# led.net
KiCad netlist of a schematic drawn in EAGLE
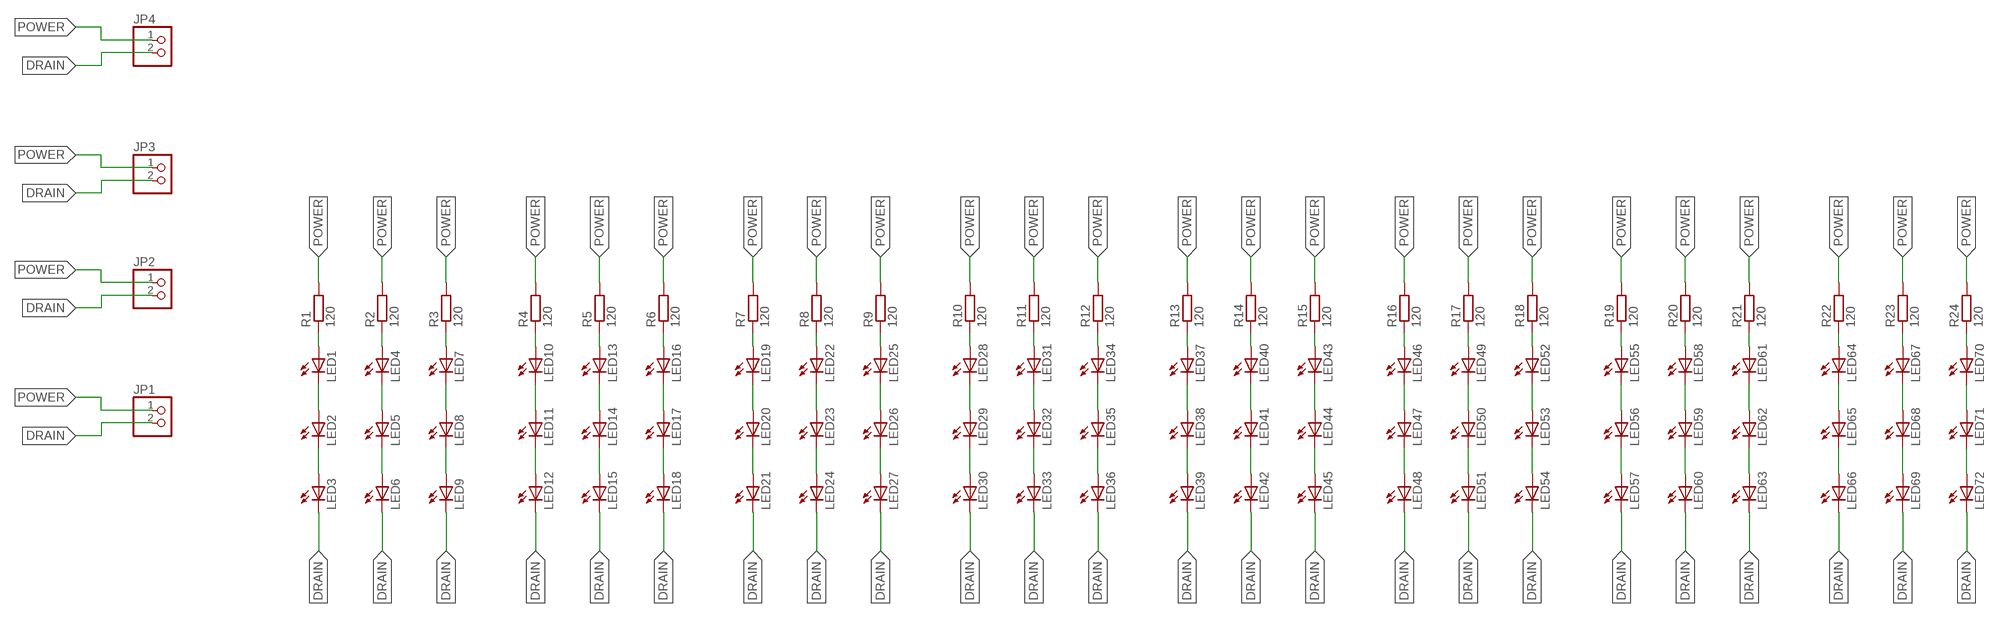
[diagram p0: schematic, sheet 1]

(export (version "E")
  (design (tool "Eeschema 10.0.6"))
  (components
    (comp (ref "JP1")
      (value "PINHD-1X2")
      (footprint "eagle-import:1X02")
      (libsource (lib "eagle-import") (part "PINHD-1X2"))
    )
    (comp (ref "JP2")
      (value "PINHD-1X2")
      (footprint "eagle-import:1X02")
      (libsource (lib "eagle-import") (part "PINHD-1X2"))
    )
    (comp (ref "JP3")
      (value "PINHD-1X2")
      (footprint "eagle-import:1X02")
      (libsource (lib "eagle-import") (part "PINHD-1X2"))
    )
    (comp (ref "JP4")
      (value "PINHD-1X2")
      (footprint "eagle-import:1X02")
      (libsource (lib "eagle-import") (part "PINHD-1X2"))
    )
    (comp (ref "LED1")
      (value "LED5MM")
      (footprint "eagle-import:LED5MM")
      (libsource (lib "eagle-import") (part "LED5MM"))
    )
    (comp (ref "LED2")
      (value "LED5MM")
      (footprint "eagle-import:LED5MM")
      (libsource (lib "eagle-import") (part "LED5MM"))
    )
    (comp (ref "LED3")
      (value "LED5MM")
      (footprint "eagle-import:LED5MM")
      (libsource (lib "eagle-import") (part "LED5MM"))
    )
    (comp (ref "LED4")
      (value "LED5MM")
      (footprint "eagle-import:LED5MM")
      (libsource (lib "eagle-import") (part "LED5MM"))
    )
    (comp (ref "LED5")
      (value "LED5MM")
      (footprint "eagle-import:LED5MM")
      (libsource (lib "eagle-import") (part "LED5MM"))
    )
    (comp (ref "LED6")
      (value "LED5MM")
      (footprint "eagle-import:LED5MM")
      (libsource (lib "eagle-import") (part "LED5MM"))
    )
    (comp (ref "LED7")
      (value "LED5MM")
      (footprint "eagle-import:LED5MM")
      (libsource (lib "eagle-import") (part "LED5MM"))
    )
    (comp (ref "LED8")
      (value "LED5MM")
      (footprint "eagle-import:LED5MM")
      (libsource (lib "eagle-import") (part "LED5MM"))
    )
    (comp (ref "LED9")
      (value "LED5MM")
      (footprint "eagle-import:LED5MM")
      (libsource (lib "eagle-import") (part "LED5MM"))
    )
    (comp (ref "LED10")
      (value "LED5MM")
      (footprint "eagle-import:LED5MM")
      (libsource (lib "eagle-import") (part "LED5MM"))
    )
    (comp (ref "LED11")
      (value "LED5MM")
      (footprint "eagle-import:LED5MM")
      (libsource (lib "eagle-import") (part "LED5MM"))
    )
    (comp (ref "LED12")
      (value "LED5MM")
      (footprint "eagle-import:LED5MM")
      (libsource (lib "eagle-import") (part "LED5MM"))
    )
    (comp (ref "LED13")
      (value "LED5MM")
      (footprint "eagle-import:LED5MM")
      (libsource (lib "eagle-import") (part "LED5MM"))
    )
    (comp (ref "LED14")
      (value "LED5MM")
      (footprint "eagle-import:LED5MM")
      (libsource (lib "eagle-import") (part "LED5MM"))
    )
    (comp (ref "LED15")
      (value "LED5MM")
      (footprint "eagle-import:LED5MM")
      (libsource (lib "eagle-import") (part "LED5MM"))
    )
    (comp (ref "LED16")
      (value "LED5MM")
      (footprint "eagle-import:LED5MM")
      (libsource (lib "eagle-import") (part "LED5MM"))
    )
    (comp (ref "LED17")
      (value "LED5MM")
      (footprint "eagle-import:LED5MM")
      (libsource (lib "eagle-import") (part "LED5MM"))
    )
    (comp (ref "LED18")
      (value "LED5MM")
      (footprint "eagle-import:LED5MM")
      (libsource (lib "eagle-import") (part "LED5MM"))
    )
    (comp (ref "LED19")
      (value "LED5MM")
      (footprint "eagle-import:LED5MM")
      (libsource (lib "eagle-import") (part "LED5MM"))
    )
    (comp (ref "LED20")
      (value "LED5MM")
      (footprint "eagle-import:LED5MM")
      (libsource (lib "eagle-import") (part "LED5MM"))
    )
    (comp (ref "LED21")
      (value "LED5MM")
      (footprint "eagle-import:LED5MM")
      (libsource (lib "eagle-import") (part "LED5MM"))
    )
    (comp (ref "LED22")
      (value "LED5MM")
      (footprint "eagle-import:LED5MM")
      (libsource (lib "eagle-import") (part "LED5MM"))
    )
    (comp (ref "LED23")
      (value "LED5MM")
      (footprint "eagle-import:LED5MM")
      (libsource (lib "eagle-import") (part "LED5MM"))
    )
    (comp (ref "LED24")
      (value "LED5MM")
      (footprint "eagle-import:LED5MM")
      (libsource (lib "eagle-import") (part "LED5MM"))
    )
    (comp (ref "LED25")
      (value "LED5MM")
      (footprint "eagle-import:LED5MM")
      (libsource (lib "eagle-import") (part "LED5MM"))
    )
    (comp (ref "LED26")
      (value "LED5MM")
      (footprint "eagle-import:LED5MM")
      (libsource (lib "eagle-import") (part "LED5MM"))
    )
    (comp (ref "LED27")
      (value "LED5MM")
      (footprint "eagle-import:LED5MM")
      (libsource (lib "eagle-import") (part "LED5MM"))
    )
    (comp (ref "LED28")
      (value "LED5MM")
      (footprint "eagle-import:LED5MM")
      (libsource (lib "eagle-import") (part "LED5MM"))
    )
    (comp (ref "LED29")
      (value "LED5MM")
      (footprint "eagle-import:LED5MM")
      (libsource (lib "eagle-import") (part "LED5MM"))
    )
    (comp (ref "LED30")
      (value "LED5MM")
      (footprint "eagle-import:LED5MM")
      (libsource (lib "eagle-import") (part "LED5MM"))
    )
    (comp (ref "LED31")
      (value "LED5MM")
      (footprint "eagle-import:LED5MM")
      (libsource (lib "eagle-import") (part "LED5MM"))
    )
    (comp (ref "LED32")
      (value "LED5MM")
      (footprint "eagle-import:LED5MM")
      (libsource (lib "eagle-import") (part "LED5MM"))
    )
    (comp (ref "LED33")
      (value "LED5MM")
      (footprint "eagle-import:LED5MM")
      (libsource (lib "eagle-import") (part "LED5MM"))
    )
    (comp (ref "LED34")
      (value "LED5MM")
      (footprint "eagle-import:LED5MM")
      (libsource (lib "eagle-import") (part "LED5MM"))
    )
    (comp (ref "LED35")
      (value "LED5MM")
      (footprint "eagle-import:LED5MM")
      (libsource (lib "eagle-import") (part "LED5MM"))
    )
    (comp (ref "LED36")
      (value "LED5MM")
      (footprint "eagle-import:LED5MM")
      (libsource (lib "eagle-import") (part "LED5MM"))
    )
    (comp (ref "LED37")
      (value "LED5MM")
      (footprint "eagle-import:LED5MM")
      (libsource (lib "eagle-import") (part "LED5MM"))
    )
    (comp (ref "LED38")
      (value "LED5MM")
      (footprint "eagle-import:LED5MM")
      (libsource (lib "eagle-import") (part "LED5MM"))
    )
    (comp (ref "LED39")
      (value "LED5MM")
      (footprint "eagle-import:LED5MM")
      (libsource (lib "eagle-import") (part "LED5MM"))
    )
    (comp (ref "LED40")
      (value "LED5MM")
      (footprint "eagle-import:LED5MM")
      (libsource (lib "eagle-import") (part "LED5MM"))
    )
    (comp (ref "LED41")
      (value "LED5MM")
      (footprint "eagle-import:LED5MM")
      (libsource (lib "eagle-import") (part "LED5MM"))
    )
    (comp (ref "LED42")
      (value "LED5MM")
      (footprint "eagle-import:LED5MM")
      (libsource (lib "eagle-import") (part "LED5MM"))
    )
    (comp (ref "LED43")
      (value "LED5MM")
      (footprint "eagle-import:LED5MM")
      (libsource (lib "eagle-import") (part "LED5MM"))
    )
    (comp (ref "LED44")
      (value "LED5MM")
      (footprint "eagle-import:LED5MM")
      (libsource (lib "eagle-import") (part "LED5MM"))
    )
    (comp (ref "LED45")
      (value "LED5MM")
      (footprint "eagle-import:LED5MM")
      (libsource (lib "eagle-import") (part "LED5MM"))
    )
    (comp (ref "LED46")
      (value "LED5MM")
      (footprint "eagle-import:LED5MM")
      (libsource (lib "eagle-import") (part "LED5MM"))
    )
    (comp (ref "LED47")
      (value "LED5MM")
      (footprint "eagle-import:LED5MM")
      (libsource (lib "eagle-import") (part "LED5MM"))
    )
    (comp (ref "LED48")
      (value "LED5MM")
      (footprint "eagle-import:LED5MM")
      (libsource (lib "eagle-import") (part "LED5MM"))
    )
    (comp (ref "LED49")
      (value "LED5MM")
      (footprint "eagle-import:LED5MM")
      (libsource (lib "eagle-import") (part "LED5MM"))
    )
    (comp (ref "LED50")
      (value "LED5MM")
      (footprint "eagle-import:LED5MM")
      (libsource (lib "eagle-import") (part "LED5MM"))
    )
    (comp (ref "LED51")
      (value "LED5MM")
      (footprint "eagle-import:LED5MM")
      (libsource (lib "eagle-import") (part "LED5MM"))
    )
    (comp (ref "LED52")
      (value "LED5MM")
      (footprint "eagle-import:LED5MM")
      (libsource (lib "eagle-import") (part "LED5MM"))
    )
    (comp (ref "LED53")
      (value "LED5MM")
      (footprint "eagle-import:LED5MM")
      (libsource (lib "eagle-import") (part "LED5MM"))
    )
    (comp (ref "LED54")
      (value "LED5MM")
      (footprint "eagle-import:LED5MM")
      (libsource (lib "eagle-import") (part "LED5MM"))
    )
    (comp (ref "LED55")
      (value "LED5MM")
      (footprint "eagle-import:LED5MM")
      (libsource (lib "eagle-import") (part "LED5MM"))
    )
    (comp (ref "LED56")
      (value "LED5MM")
      (footprint "eagle-import:LED5MM")
      (libsource (lib "eagle-import") (part "LED5MM"))
    )
    (comp (ref "LED57")
      (value "LED5MM")
      (footprint "eagle-import:LED5MM")
      (libsource (lib "eagle-import") (part "LED5MM"))
    )
    (comp (ref "LED58")
      (value "LED5MM")
      (footprint "eagle-import:LED5MM")
      (libsource (lib "eagle-import") (part "LED5MM"))
    )
    (comp (ref "LED59")
      (value "LED5MM")
      (footprint "eagle-import:LED5MM")
      (libsource (lib "eagle-import") (part "LED5MM"))
    )
    (comp (ref "LED60")
      (value "LED5MM")
      (footprint "eagle-import:LED5MM")
      (libsource (lib "eagle-import") (part "LED5MM"))
    )
    (comp (ref "LED61")
      (value "LED5MM")
      (footprint "eagle-import:LED5MM")
      (libsource (lib "eagle-import") (part "LED5MM"))
    )
    (comp (ref "LED62")
      (value "LED5MM")
      (footprint "eagle-import:LED5MM")
      (libsource (lib "eagle-import") (part "LED5MM"))
    )
    (comp (ref "LED63")
      (value "LED5MM")
      (footprint "eagle-import:LED5MM")
      (libsource (lib "eagle-import") (part "LED5MM"))
    )
    (comp (ref "LED64")
      (value "LED5MM")
      (footprint "eagle-import:LED5MM")
      (libsource (lib "eagle-import") (part "LED5MM"))
    )
    (comp (ref "LED65")
      (value "LED5MM")
      (footprint "eagle-import:LED5MM")
      (libsource (lib "eagle-import") (part "LED5MM"))
    )
    (comp (ref "LED66")
      (value "LED5MM")
      (footprint "eagle-import:LED5MM")
      (libsource (lib "eagle-import") (part "LED5MM"))
    )
    (comp (ref "LED67")
      (value "LED5MM")
      (footprint "eagle-import:LED5MM")
      (libsource (lib "eagle-import") (part "LED5MM"))
    )
    (comp (ref "LED68")
      (value "LED5MM")
      (footprint "eagle-import:LED5MM")
      (libsource (lib "eagle-import") (part "LED5MM"))
    )
    (comp (ref "LED69")
      (value "LED5MM")
      (footprint "eagle-import:LED5MM")
      (libsource (lib "eagle-import") (part "LED5MM"))
    )
    (comp (ref "LED70")
      (value "LED5MM")
      (footprint "eagle-import:LED5MM")
      (libsource (lib "eagle-import") (part "LED5MM"))
    )
    (comp (ref "LED71")
      (value "LED5MM")
      (footprint "eagle-import:LED5MM")
      (libsource (lib "eagle-import") (part "LED5MM"))
    )
    (comp (ref "LED72")
      (value "LED5MM")
      (footprint "eagle-import:LED5MM")
      (libsource (lib "eagle-import") (part "LED5MM"))
    )
    (comp (ref "R1")
      (value "120")
      (footprint "eagle-import:R0805")
      (libsource (lib "eagle-import") (part "R-EU_R0805"))
    )
    (comp (ref "R2")
      (value "120")
      (footprint "eagle-import:R0805")
      (libsource (lib "eagle-import") (part "R-EU_R0805"))
    )
    (comp (ref "R3")
      (value "120")
      (footprint "eagle-import:R0805")
      (libsource (lib "eagle-import") (part "R-EU_R0805"))
    )
    (comp (ref "R4")
      (value "120")
      (footprint "eagle-import:R0805")
      (libsource (lib "eagle-import") (part "R-EU_R0805"))
    )
    (comp (ref "R5")
      (value "120")
      (footprint "eagle-import:R0805")
      (libsource (lib "eagle-import") (part "R-EU_R0805"))
    )
    (comp (ref "R6")
      (value "120")
      (footprint "eagle-import:R0805")
      (libsource (lib "eagle-import") (part "R-EU_R0805"))
    )
    (comp (ref "R7")
      (value "120")
      (footprint "eagle-import:R0805")
      (libsource (lib "eagle-import") (part "R-EU_R0805"))
    )
    (comp (ref "R8")
      (value "120")
      (footprint "eagle-import:R0805")
      (libsource (lib "eagle-import") (part "R-EU_R0805"))
    )
    (comp (ref "R9")
      (value "120")
      (footprint "eagle-import:R0805")
      (libsource (lib "eagle-import") (part "R-EU_R0805"))
    )
    (comp (ref "R10")
      (value "120")
      (footprint "eagle-import:R0805")
      (libsource (lib "eagle-import") (part "R-EU_R0805"))
    )
    (comp (ref "R11")
      (value "120")
      (footprint "eagle-import:R0805")
      (libsource (lib "eagle-import") (part "R-EU_R0805"))
    )
    (comp (ref "R12")
      (value "120")
      (footprint "eagle-import:R0805")
      (libsource (lib "eagle-import") (part "R-EU_R0805"))
    )
    (comp (ref "R13")
      (value "120")
      (footprint "eagle-import:R0805")
      (libsource (lib "eagle-import") (part "R-EU_R0805"))
    )
    (comp (ref "R14")
      (value "120")
      (footprint "eagle-import:R0805")
      (libsource (lib "eagle-import") (part "R-EU_R0805"))
    )
    (comp (ref "R15")
      (value "120")
      (footprint "eagle-import:R0805")
      (libsource (lib "eagle-import") (part "R-EU_R0805"))
    )
    (comp (ref "R16")
      (value "120")
      (footprint "eagle-import:R0805")
      (libsource (lib "eagle-import") (part "R-EU_R0805"))
    )
    (comp (ref "R17")
      (value "120")
      (footprint "eagle-import:R0805")
      (libsource (lib "eagle-import") (part "R-EU_R0805"))
    )
    (comp (ref "R18")
      (value "120")
      (footprint "eagle-import:R0805")
      (libsource (lib "eagle-import") (part "R-EU_R0805"))
    )
    (comp (ref "R19")
      (value "120")
      (footprint "eagle-import:R0805")
      (libsource (lib "eagle-import") (part "R-EU_R0805"))
    )
    (comp (ref "R20")
      (value "120")
      (footprint "eagle-import:R0805")
      (libsource (lib "eagle-import") (part "R-EU_R0805"))
    )
    (comp (ref "R21")
      (value "120")
      (footprint "eagle-import:R0805")
      (libsource (lib "eagle-import") (part "R-EU_R0805"))
    )
    (comp (ref "R22")
      (value "120")
      (footprint "eagle-import:R0805")
      (libsource (lib "eagle-import") (part "R-EU_R0805"))
    )
    (comp (ref "R23")
      (value "120")
      (footprint "eagle-import:R0805")
      (libsource (lib "eagle-import") (part "R-EU_R0805"))
    )
    (comp (ref "R24")
      (value "120")
      (footprint "eagle-import:R0805")
      (libsource (lib "eagle-import") (part "R-EU_R0805"))
    )
  )
  (nets
    (net (code "1") (name "DRAIN") (class "Default")
      (node (ref "JP1") (pin "2") (pinfunction "2_2") (pintype "passive"))
      (node (ref "JP2") (pin "2") (pinfunction "2_2") (pintype "passive"))
      (node (ref "JP3") (pin "2") (pinfunction "2_2") (pintype "passive"))
      (node (ref "JP4") (pin "2") (pinfunction "2_2") (pintype "passive"))
      (node (ref "LED12") (pin "K") (pinfunction "C_K") (pintype "passive"))
      (node (ref "LED15") (pin "K") (pinfunction "C_K") (pintype "passive"))
      (node (ref "LED18") (pin "K") (pinfunction "C_K") (pintype "passive"))
      (node (ref "LED21") (pin "K") (pinfunction "C_K") (pintype "passive"))
      (node (ref "LED24") (pin "K") (pinfunction "C_K") (pintype "passive"))
      (node (ref "LED27") (pin "K") (pinfunction "C_K") (pintype "passive"))
      (node (ref "LED3") (pin "K") (pinfunction "C_K") (pintype "passive"))
      (node (ref "LED30") (pin "K") (pinfunction "C_K") (pintype "passive"))
      (node (ref "LED33") (pin "K") (pinfunction "C_K") (pintype "passive"))
      (node (ref "LED36") (pin "K") (pinfunction "C_K") (pintype "passive"))
      (node (ref "LED39") (pin "K") (pinfunction "C_K") (pintype "passive"))
      (node (ref "LED42") (pin "K") (pinfunction "C_K") (pintype "passive"))
      (node (ref "LED45") (pin "K") (pinfunction "C_K") (pintype "passive"))
      (node (ref "LED48") (pin "K") (pinfunction "C_K") (pintype "passive"))
      (node (ref "LED51") (pin "K") (pinfunction "C_K") (pintype "passive"))
      (node (ref "LED54") (pin "K") (pinfunction "C_K") (pintype "passive"))
      (node (ref "LED57") (pin "K") (pinfunction "C_K") (pintype "passive"))
      (node (ref "LED6") (pin "K") (pinfunction "C_K") (pintype "passive"))
      (node (ref "LED60") (pin "K") (pinfunction "C_K") (pintype "passive"))
      (node (ref "LED63") (pin "K") (pinfunction "C_K") (pintype "passive"))
      (node (ref "LED66") (pin "K") (pinfunction "C_K") (pintype "passive"))
      (node (ref "LED69") (pin "K") (pinfunction "C_K") (pintype "passive"))
      (node (ref "LED72") (pin "K") (pinfunction "C_K") (pintype "passive"))
      (node (ref "LED9") (pin "K") (pinfunction "C_K") (pintype "passive"))
    )
    (net (code "2") (name "Net-(LED1-C)") (class "Default")
      (node (ref "LED1") (pin "K") (pinfunction "C_K") (pintype "passive"))
      (node (ref "LED2") (pin "A") (pinfunction "A_A") (pintype "passive"))
    )
    (net (code "3") (name "Net-(LED1-PadA)") (class "Default")
      (node (ref "LED1") (pin "A") (pinfunction "A_A") (pintype "passive"))
      (node (ref "R1") (pin "1") (pinfunction "1_1") (pintype "passive"))
    )
    (net (code "4") (name "Net-(LED2-C)") (class "Default")
      (node (ref "LED2") (pin "K") (pinfunction "C_K") (pintype "passive"))
      (node (ref "LED3") (pin "A") (pinfunction "A_A") (pintype "passive"))
    )
    (net (code "5") (name "Net-(LED4-C)") (class "Default")
      (node (ref "LED4") (pin "K") (pinfunction "C_K") (pintype "passive"))
      (node (ref "LED5") (pin "A") (pinfunction "A_A") (pintype "passive"))
    )
    (net (code "6") (name "Net-(LED4-PadA)") (class "Default")
      (node (ref "LED4") (pin "A") (pinfunction "A_A") (pintype "passive"))
      (node (ref "R2") (pin "1") (pinfunction "1_1") (pintype "passive"))
    )
    (net (code "7") (name "Net-(LED5-C)") (class "Default")
      (node (ref "LED5") (pin "K") (pinfunction "C_K") (pintype "passive"))
      (node (ref "LED6") (pin "A") (pinfunction "A_A") (pintype "passive"))
    )
    (net (code "8") (name "Net-(LED7-C)") (class "Default")
      (node (ref "LED7") (pin "K") (pinfunction "C_K") (pintype "passive"))
      (node (ref "LED8") (pin "A") (pinfunction "A_A") (pintype "passive"))
    )
    (net (code "9") (name "Net-(LED7-PadA)") (class "Default")
      (node (ref "LED7") (pin "A") (pinfunction "A_A") (pintype "passive"))
      (node (ref "R3") (pin "1") (pinfunction "1_1") (pintype "passive"))
    )
    (net (code "10") (name "Net-(LED8-C)") (class "Default")
      (node (ref "LED8") (pin "K") (pinfunction "C_K") (pintype "passive"))
      (node (ref "LED9") (pin "A") (pinfunction "A_A") (pintype "passive"))
    )
    (net (code "11") (name "Net-(LED10-C)") (class "Default")
      (node (ref "LED10") (pin "K") (pinfunction "C_K") (pintype "passive"))
      (node (ref "LED11") (pin "A") (pinfunction "A_A") (pintype "passive"))
    )
    (net (code "12") (name "Net-(LED10-PadA)") (class "Default")
      (node (ref "LED10") (pin "A") (pinfunction "A_A") (pintype "passive"))
      (node (ref "R4") (pin "1") (pinfunction "1_1") (pintype "passive"))
    )
    (net (code "13") (name "Net-(LED11-C)") (class "Default")
      (node (ref "LED11") (pin "K") (pinfunction "C_K") (pintype "passive"))
      (node (ref "LED12") (pin "A") (pinfunction "A_A") (pintype "passive"))
    )
    (net (code "14") (name "Net-(LED13-C)") (class "Default")
      (node (ref "LED13") (pin "K") (pinfunction "C_K") (pintype "passive"))
      (node (ref "LED14") (pin "A") (pinfunction "A_A") (pintype "passive"))
    )
    (net (code "15") (name "Net-(LED13-PadA)") (class "Default")
      (node (ref "LED13") (pin "A") (pinfunction "A_A") (pintype "passive"))
      (node (ref "R5") (pin "1") (pinfunction "1_1") (pintype "passive"))
    )
    (net (code "16") (name "Net-(LED14-C)") (class "Default")
      (node (ref "LED14") (pin "K") (pinfunction "C_K") (pintype "passive"))
      (node (ref "LED15") (pin "A") (pinfunction "A_A") (pintype "passive"))
    )
    (net (code "17") (name "Net-(LED16-C)") (class "Default")
      (node (ref "LED16") (pin "K") (pinfunction "C_K") (pintype "passive"))
      (node (ref "LED17") (pin "A") (pinfunction "A_A") (pintype "passive"))
    )
    (net (code "18") (name "Net-(LED16-PadA)") (class "Default")
      (node (ref "LED16") (pin "A") (pinfunction "A_A") (pintype "passive"))
      (node (ref "R6") (pin "1") (pinfunction "1_1") (pintype "passive"))
    )
    (net (code "19") (name "Net-(LED17-C)") (class "Default")
      (node (ref "LED17") (pin "K") (pinfunction "C_K") (pintype "passive"))
      (node (ref "LED18") (pin "A") (pinfunction "A_A") (pintype "passive"))
    )
    (net (code "20") (name "Net-(LED19-C)") (class "Default")
      (node (ref "LED19") (pin "K") (pinfunction "C_K") (pintype "passive"))
      (node (ref "LED20") (pin "A") (pinfunction "A_A") (pintype "passive"))
    )
    (net (code "21") (name "Net-(LED19-PadA)") (class "Default")
      (node (ref "LED19") (pin "A") (pinfunction "A_A") (pintype "passive"))
      (node (ref "R7") (pin "1") (pinfunction "1_1") (pintype "passive"))
    )
    (net (code "22") (name "Net-(LED20-C)") (class "Default")
      (node (ref "LED20") (pin "K") (pinfunction "C_K") (pintype "passive"))
      (node (ref "LED21") (pin "A") (pinfunction "A_A") (pintype "passive"))
    )
    (net (code "23") (name "Net-(LED22-C)") (class "Default")
      (node (ref "LED22") (pin "K") (pinfunction "C_K") (pintype "passive"))
      (node (ref "LED23") (pin "A") (pinfunction "A_A") (pintype "passive"))
    )
    (net (code "24") (name "Net-(LED22-PadA)") (class "Default")
      (node (ref "LED22") (pin "A") (pinfunction "A_A") (pintype "passive"))
      (node (ref "R8") (pin "1") (pinfunction "1_1") (pintype "passive"))
    )
    (net (code "25") (name "Net-(LED23-C)") (class "Default")
      (node (ref "LED23") (pin "K") (pinfunction "C_K") (pintype "passive"))
      (node (ref "LED24") (pin "A") (pinfunction "A_A") (pintype "passive"))
    )
    (net (code "26") (name "Net-(LED25-C)") (class "Default")
      (node (ref "LED25") (pin "K") (pinfunction "C_K") (pintype "passive"))
      (node (ref "LED26") (pin "A") (pinfunction "A_A") (pintype "passive"))
    )
    (net (code "27") (name "Net-(LED25-PadA)") (class "Default")
      (node (ref "LED25") (pin "A") (pinfunction "A_A") (pintype "passive"))
      (node (ref "R9") (pin "1") (pinfunction "1_1") (pintype "passive"))
    )
    (net (code "28") (name "Net-(LED26-C)") (class "Default")
      (node (ref "LED26") (pin "K") (pinfunction "C_K") (pintype "passive"))
      (node (ref "LED27") (pin "A") (pinfunction "A_A") (pintype "passive"))
    )
    (net (code "29") (name "Net-(LED28-C)") (class "Default")
      (node (ref "LED28") (pin "K") (pinfunction "C_K") (pintype "passive"))
      (node (ref "LED29") (pin "A") (pinfunction "A_A") (pintype "passive"))
    )
    (net (code "30") (name "Net-(LED28-PadA)") (class "Default")
      (node (ref "LED28") (pin "A") (pinfunction "A_A") (pintype "passive"))
      (node (ref "R10") (pin "1") (pinfunction "1_1") (pintype "passive"))
    )
    (net (code "31") (name "Net-(LED29-C)") (class "Default")
      (node (ref "LED29") (pin "K") (pinfunction "C_K") (pintype "passive"))
      (node (ref "LED30") (pin "A") (pinfunction "A_A") (pintype "passive"))
    )
    (net (code "32") (name "Net-(LED31-C)") (class "Default")
      (node (ref "LED31") (pin "K") (pinfunction "C_K") (pintype "passive"))
      (node (ref "LED32") (pin "A") (pinfunction "A_A") (pintype "passive"))
    )
    (net (code "33") (name "Net-(LED31-PadA)") (class "Default")
      (node (ref "LED31") (pin "A") (pinfunction "A_A") (pintype "passive"))
      (node (ref "R11") (pin "1") (pinfunction "1_1") (pintype "passive"))
    )
    (net (code "34") (name "Net-(LED32-C)") (class "Default")
      (node (ref "LED32") (pin "K") (pinfunction "C_K") (pintype "passive"))
      (node (ref "LED33") (pin "A") (pinfunction "A_A") (pintype "passive"))
    )
    (net (code "35") (name "Net-(LED34-C)") (class "Default")
      (node (ref "LED34") (pin "K") (pinfunction "C_K") (pintype "passive"))
      (node (ref "LED35") (pin "A") (pinfunction "A_A") (pintype "passive"))
    )
    (net (code "36") (name "Net-(LED34-PadA)") (class "Default")
      (node (ref "LED34") (pin "A") (pinfunction "A_A") (pintype "passive"))
      (node (ref "R12") (pin "1") (pinfunction "1_1") (pintype "passive"))
    )
    (net (code "37") (name "Net-(LED35-C)") (class "Default")
      (node (ref "LED35") (pin "K") (pinfunction "C_K") (pintype "passive"))
      (node (ref "LED36") (pin "A") (pinfunction "A_A") (pintype "passive"))
    )
    (net (code "38") (name "Net-(LED37-C)") (class "Default")
      (node (ref "LED37") (pin "K") (pinfunction "C_K") (pintype "passive"))
      (node (ref "LED38") (pin "A") (pinfunction "A_A") (pintype "passive"))
    )
    (net (code "39") (name "Net-(LED37-PadA)") (class "Default")
      (node (ref "LED37") (pin "A") (pinfunction "A_A") (pintype "passive"))
      (node (ref "R13") (pin "1") (pinfunction "1_1") (pintype "passive"))
    )
    (net (code "40") (name "Net-(LED38-C)") (class "Default")
      (node (ref "LED38") (pin "K") (pinfunction "C_K") (pintype "passive"))
      (node (ref "LED39") (pin "A") (pinfunction "A_A") (pintype "passive"))
    )
    (net (code "41") (name "Net-(LED40-C)") (class "Default")
      (node (ref "LED40") (pin "K") (pinfunction "C_K") (pintype "passive"))
      (node (ref "LED41") (pin "A") (pinfunction "A_A") (pintype "passive"))
    )
    (net (code "42") (name "Net-(LED40-PadA)") (class "Default")
      (node (ref "LED40") (pin "A") (pinfunction "A_A") (pintype "passive"))
      (node (ref "R14") (pin "1") (pinfunction "1_1") (pintype "passive"))
    )
    (net (code "43") (name "Net-(LED41-C)") (class "Default")
      (node (ref "LED41") (pin "K") (pinfunction "C_K") (pintype "passive"))
      (node (ref "LED42") (pin "A") (pinfunction "A_A") (pintype "passive"))
    )
    (net (code "44") (name "Net-(LED43-C)") (class "Default")
      (node (ref "LED43") (pin "K") (pinfunction "C_K") (pintype "passive"))
      (node (ref "LED44") (pin "A") (pinfunction "A_A") (pintype "passive"))
    )
    (net (code "45") (name "Net-(LED43-PadA)") (class "Default")
      (node (ref "LED43") (pin "A") (pinfunction "A_A") (pintype "passive"))
      (node (ref "R15") (pin "1") (pinfunction "1_1") (pintype "passive"))
    )
    (net (code "46") (name "Net-(LED44-C)") (class "Default")
      (node (ref "LED44") (pin "K") (pinfunction "C_K") (pintype "passive"))
      (node (ref "LED45") (pin "A") (pinfunction "A_A") (pintype "passive"))
    )
    (net (code "47") (name "Net-(LED46-C)") (class "Default")
      (node (ref "LED46") (pin "K") (pinfunction "C_K") (pintype "passive"))
      (node (ref "LED47") (pin "A") (pinfunction "A_A") (pintype "passive"))
    )
    (net (code "48") (name "Net-(LED46-PadA)") (class "Default")
      (node (ref "LED46") (pin "A") (pinfunction "A_A") (pintype "passive"))
      (node (ref "R16") (pin "1") (pinfunction "1_1") (pintype "passive"))
    )
    (net (code "49") (name "Net-(LED47-C)") (class "Default")
      (node (ref "LED47") (pin "K") (pinfunction "C_K") (pintype "passive"))
      (node (ref "LED48") (pin "A") (pinfunction "A_A") (pintype "passive"))
    )
    (net (code "50") (name "Net-(LED49-C)") (class "Default")
      (node (ref "LED49") (pin "K") (pinfunction "C_K") (pintype "passive"))
      (node (ref "LED50") (pin "A") (pinfunction "A_A") (pintype "passive"))
    )
    (net (code "51") (name "Net-(LED49-PadA)") (class "Default")
      (node (ref "LED49") (pin "A") (pinfunction "A_A") (pintype "passive"))
      (node (ref "R17") (pin "1") (pinfunction "1_1") (pintype "passive"))
    )
    (net (code "52") (name "Net-(LED50-C)") (class "Default")
      (node (ref "LED50") (pin "K") (pinfunction "C_K") (pintype "passive"))
      (node (ref "LED51") (pin "A") (pinfunction "A_A") (pintype "passive"))
    )
    (net (code "53") (name "Net-(LED52-C)") (class "Default")
      (node (ref "LED52") (pin "K") (pinfunction "C_K") (pintype "passive"))
      (node (ref "LED53") (pin "A") (pinfunction "A_A") (pintype "passive"))
    )
    (net (code "54") (name "Net-(LED52-PadA)") (class "Default")
      (node (ref "LED52") (pin "A") (pinfunction "A_A") (pintype "passive"))
      (node (ref "R18") (pin "1") (pinfunction "1_1") (pintype "passive"))
    )
    (net (code "55") (name "Net-(LED53-C)") (class "Default")
      (node (ref "LED53") (pin "K") (pinfunction "C_K") (pintype "passive"))
      (node (ref "LED54") (pin "A") (pinfunction "A_A") (pintype "passive"))
    )
    (net (code "56") (name "Net-(LED55-C)") (class "Default")
      (node (ref "LED55") (pin "K") (pinfunction "C_K") (pintype "passive"))
      (node (ref "LED56") (pin "A") (pinfunction "A_A") (pintype "passive"))
    )
    (net (code "57") (name "Net-(LED55-PadA)") (class "Default")
      (node (ref "LED55") (pin "A") (pinfunction "A_A") (pintype "passive"))
      (node (ref "R19") (pin "1") (pinfunction "1_1") (pintype "passive"))
    )
    (net (code "58") (name "Net-(LED56-C)") (class "Default")
      (node (ref "LED56") (pin "K") (pinfunction "C_K") (pintype "passive"))
      (node (ref "LED57") (pin "A") (pinfunction "A_A") (pintype "passive"))
    )
    (net (code "59") (name "Net-(LED58-C)") (class "Default")
      (node (ref "LED58") (pin "K") (pinfunction "C_K") (pintype "passive"))
      (node (ref "LED59") (pin "A") (pinfunction "A_A") (pintype "passive"))
    )
    (net (code "60") (name "Net-(LED58-PadA)") (class "Default")
      (node (ref "LED58") (pin "A") (pinfunction "A_A") (pintype "passive"))
      (node (ref "R20") (pin "1") (pinfunction "1_1") (pintype "passive"))
    )
    (net (code "61") (name "Net-(LED59-C)") (class "Default")
      (node (ref "LED59") (pin "K") (pinfunction "C_K") (pintype "passive"))
      (node (ref "LED60") (pin "A") (pinfunction "A_A") (pintype "passive"))
    )
    (net (code "62") (name "Net-(LED61-C)") (class "Default")
      (node (ref "LED61") (pin "K") (pinfunction "C_K") (pintype "passive"))
      (node (ref "LED62") (pin "A") (pinfunction "A_A") (pintype "passive"))
    )
    (net (code "63") (name "Net-(LED61-PadA)") (class "Default")
      (node (ref "LED61") (pin "A") (pinfunction "A_A") (pintype "passive"))
      (node (ref "R21") (pin "1") (pinfunction "1_1") (pintype "passive"))
    )
    (net (code "64") (name "Net-(LED62-C)") (class "Default")
      (node (ref "LED62") (pin "K") (pinfunction "C_K") (pintype "passive"))
      (node (ref "LED63") (pin "A") (pinfunction "A_A") (pintype "passive"))
    )
    (net (code "65") (name "Net-(LED64-C)") (class "Default")
      (node (ref "LED64") (pin "K") (pinfunction "C_K") (pintype "passive"))
      (node (ref "LED65") (pin "A") (pinfunction "A_A") (pintype "passive"))
    )
    (net (code "66") (name "Net-(LED64-PadA)") (class "Default")
      (node (ref "LED64") (pin "A") (pinfunction "A_A") (pintype "passive"))
      (node (ref "R22") (pin "1") (pinfunction "1_1") (pintype "passive"))
    )
    (net (code "67") (name "Net-(LED65-C)") (class "Default")
      (node (ref "LED65") (pin "K") (pinfunction "C_K") (pintype "passive"))
      (node (ref "LED66") (pin "A") (pinfunction "A_A") (pintype "passive"))
    )
    (net (code "68") (name "Net-(LED67-C)") (class "Default")
      (node (ref "LED67") (pin "K") (pinfunction "C_K") (pintype "passive"))
      (node (ref "LED68") (pin "A") (pinfunction "A_A") (pintype "passive"))
    )
    (net (code "69") (name "Net-(LED67-PadA)") (class "Default")
      (node (ref "LED67") (pin "A") (pinfunction "A_A") (pintype "passive"))
      (node (ref "R23") (pin "1") (pinfunction "1_1") (pintype "passive"))
    )
    (net (code "70") (name "Net-(LED68-C)") (class "Default")
      (node (ref "LED68") (pin "K") (pinfunction "C_K") (pintype "passive"))
      (node (ref "LED69") (pin "A") (pinfunction "A_A") (pintype "passive"))
    )
    (net (code "71") (name "Net-(LED70-C)") (class "Default")
      (node (ref "LED70") (pin "K") (pinfunction "C_K") (pintype "passive"))
      (node (ref "LED71") (pin "A") (pinfunction "A_A") (pintype "passive"))
    )
    (net (code "72") (name "Net-(LED70-PadA)") (class "Default")
      (node (ref "LED70") (pin "A") (pinfunction "A_A") (pintype "passive"))
      (node (ref "R24") (pin "1") (pinfunction "1_1") (pintype "passive"))
    )
    (net (code "73") (name "Net-(LED71-C)") (class "Default")
      (node (ref "LED71") (pin "K") (pinfunction "C_K") (pintype "passive"))
      (node (ref "LED72") (pin "A") (pinfunction "A_A") (pintype "passive"))
    )
    (net (code "74") (name "POWER") (class "Default")
      (node (ref "JP1") (pin "1") (pinfunction "1_1") (pintype "passive"))
      (node (ref "JP2") (pin "1") (pinfunction "1_1") (pintype "passive"))
      (node (ref "JP3") (pin "1") (pinfunction "1_1") (pintype "passive"))
      (node (ref "JP4") (pin "1") (pinfunction "1_1") (pintype "passive"))
      (node (ref "R1") (pin "2") (pinfunction "2_2") (pintype "passive"))
      (node (ref "R10") (pin "2") (pinfunction "2_2") (pintype "passive"))
      (node (ref "R11") (pin "2") (pinfunction "2_2") (pintype "passive"))
      (node (ref "R12") (pin "2") (pinfunction "2_2") (pintype "passive"))
      (node (ref "R13") (pin "2") (pinfunction "2_2") (pintype "passive"))
      (node (ref "R14") (pin "2") (pinfunction "2_2") (pintype "passive"))
      (node (ref "R15") (pin "2") (pinfunction "2_2") (pintype "passive"))
      (node (ref "R16") (pin "2") (pinfunction "2_2") (pintype "passive"))
      (node (ref "R17") (pin "2") (pinfunction "2_2") (pintype "passive"))
      (node (ref "R18") (pin "2") (pinfunction "2_2") (pintype "passive"))
      (node (ref "R19") (pin "2") (pinfunction "2_2") (pintype "passive"))
      (node (ref "R2") (pin "2") (pinfunction "2_2") (pintype "passive"))
      (node (ref "R20") (pin "2") (pinfunction "2_2") (pintype "passive"))
      (node (ref "R21") (pin "2") (pinfunction "2_2") (pintype "passive"))
      (node (ref "R22") (pin "2") (pinfunction "2_2") (pintype "passive"))
      (node (ref "R23") (pin "2") (pinfunction "2_2") (pintype "passive"))
      (node (ref "R24") (pin "2") (pinfunction "2_2") (pintype "passive"))
      (node (ref "R3") (pin "2") (pinfunction "2_2") (pintype "passive"))
      (node (ref "R4") (pin "2") (pinfunction "2_2") (pintype "passive"))
      (node (ref "R5") (pin "2") (pinfunction "2_2") (pintype "passive"))
      (node (ref "R6") (pin "2") (pinfunction "2_2") (pintype "passive"))
      (node (ref "R7") (pin "2") (pinfunction "2_2") (pintype "passive"))
      (node (ref "R8") (pin "2") (pinfunction "2_2") (pintype "passive"))
      (node (ref "R9") (pin "2") (pinfunction "2_2") (pintype "passive"))
    )
  )
)
